# sensor.net
KiCad netlist of a schematic drawn in Altium Designer
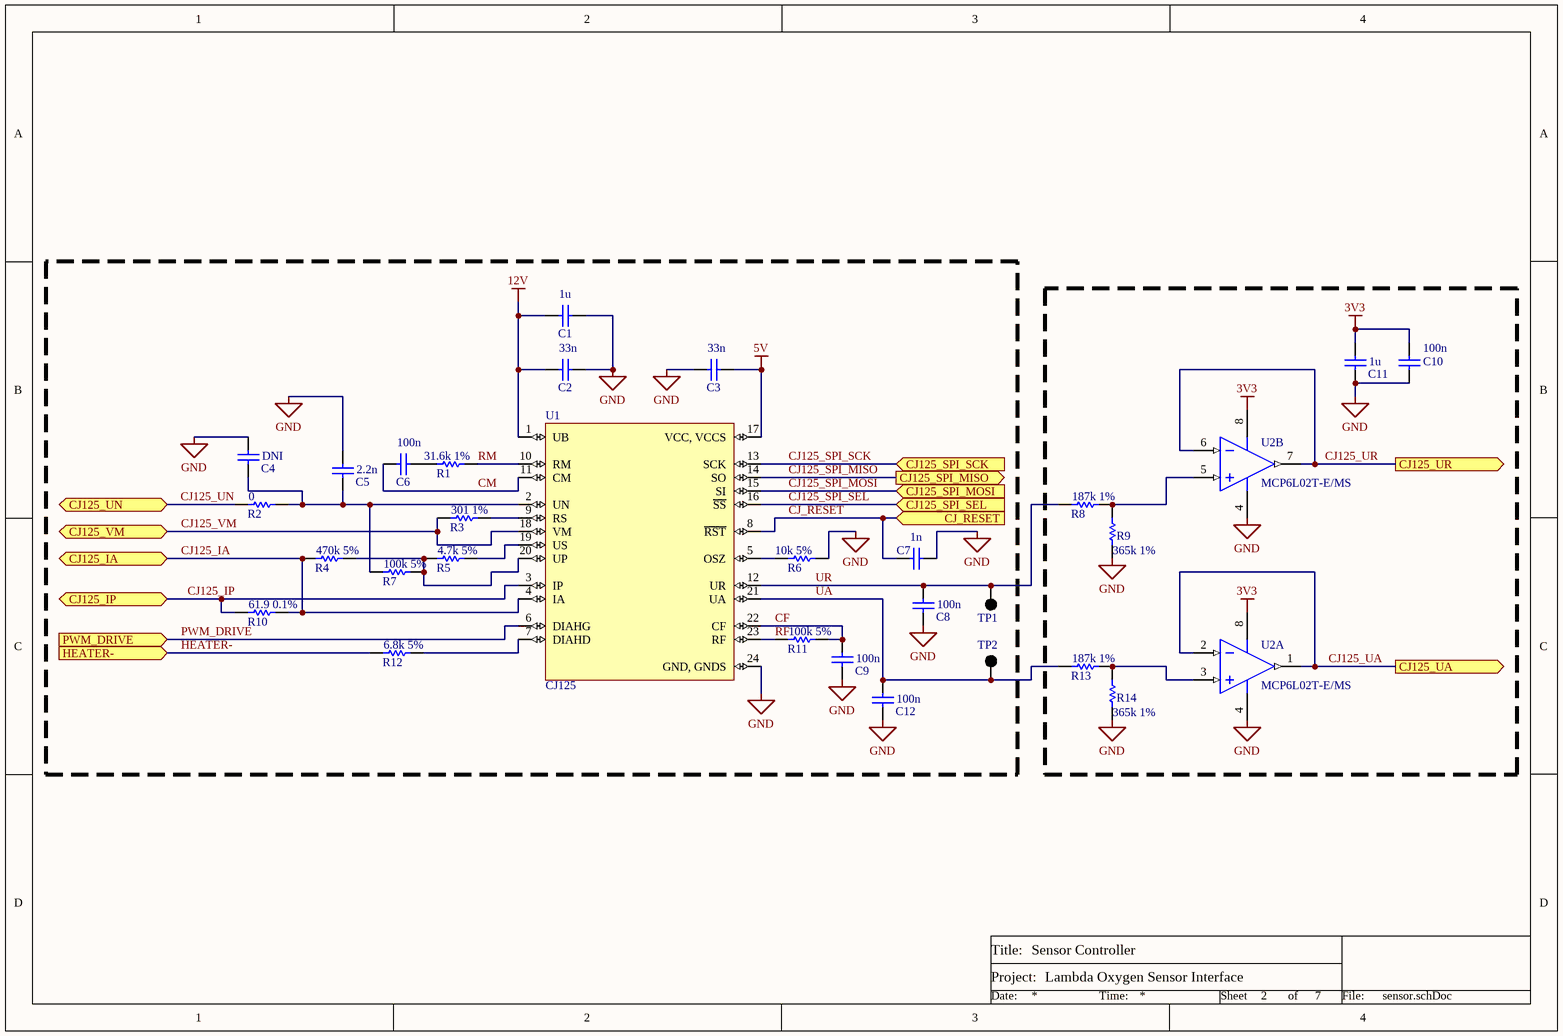
[diagram p0: sensor.schDoc]

(export (version "E")
  (design (tool "Eeschema 10.0.6"))
  (components
    (comp (ref "C1")
      (value "1u")
      (footprint "1206")
      (description "Generic 1206 Capacitor")
      (libsource (lib "symbol_library") (part "C_1206"))
    )
    (comp (ref "C2")
      (value "33n")
      (footprint "0805")
      (description "Generic 0805 Capacitor")
      (libsource (lib "symbol_library") (part "C_0805"))
    )
    (comp (ref "C3")
      (value "33n")
      (footprint "0805")
      (description "Generic 0805 Capacitor")
      (libsource (lib "symbol_library") (part "C_0805"))
    )
    (comp (ref "C4")
      (value "DNI")
      (footprint "0805")
      (description "Generic 0805 Capacitor")
      (libsource (lib "symbol_library") (part "C_0805"))
    )
    (comp (ref "C5")
      (value "2.2n")
      (footprint "0805")
      (description "Generic 0805 Capacitor")
      (libsource (lib "symbol_library") (part "C_0805"))
    )
    (comp (ref "C6")
      (value "100n")
      (footprint "0805")
      (description "Generic 0805 Capacitor")
      (libsource (lib "symbol_library") (part "C_0805"))
    )
    (comp (ref "C7")
      (value "1n")
      (footprint "0805")
      (description "Generic 0805 Capacitor")
      (libsource (lib "symbol_library") (part "C_0805"))
    )
    (comp (ref "C8")
      (value "100n")
      (footprint "0805")
      (description "Generic 0805 Capacitor")
      (libsource (lib "symbol_library") (part "C_0805"))
    )
    (comp (ref "C9")
      (value "100n")
      (footprint "0805")
      (description "Generic 0805 Capacitor")
      (libsource (lib "symbol_library") (part "C_0805"))
    )
    (comp (ref "C10")
      (value "100n")
      (footprint "0805")
      (description "Generic 0805 Capacitor")
      (libsource (lib "symbol_library") (part "C_0805"))
    )
    (comp (ref "C11")
      (value "1u")
      (footprint "1206")
      (description "Generic 1206 Capacitor")
      (libsource (lib "symbol_library") (part "C_1206"))
    )
    (comp (ref "C12")
      (value "100n")
      (footprint "0805")
      (description "Generic 0805 Capacitor")
      (libsource (lib "symbol_library") (part "C_0805"))
    )
    (comp (ref "R1")
      (value "31.6k 1%")
      (footprint "0603")
      (description "Generic 0603 Resistor")
      (libsource (lib "symbol_library") (part "R_0603"))
    )
    (comp (ref "R2")
      (value "0")
      (footprint "0603")
      (description "Generic 0603 Resistor")
      (libsource (lib "symbol_library") (part "R_0603"))
    )
    (comp (ref "R3")
      (value "301 1%")
      (footprint "0603")
      (description "Generic 0603 Resistor")
      (libsource (lib "symbol_library") (part "R_0603"))
    )
    (comp (ref "R4")
      (value "470k 5%")
      (footprint "0603")
      (description "Generic 0603 Resistor")
      (libsource (lib "symbol_library") (part "R_0603"))
    )
    (comp (ref "R5")
      (value "4.7k 5%")
      (footprint "0603")
      (description "Generic 0603 Resistor")
      (libsource (lib "symbol_library") (part "R_0603"))
    )
    (comp (ref "R6")
      (value "10k 5%")
      (footprint "0603")
      (description "Generic 0603 Resistor")
      (libsource (lib "symbol_library") (part "R_0603"))
    )
    (comp (ref "R7")
      (value "100k 5%")
      (footprint "0603")
      (description "Generic 0603 Resistor")
      (libsource (lib "symbol_library") (part "R_0603"))
    )
    (comp (ref "R8")
      (value "187k 1%")
      (footprint "0603")
      (description "Generic 0603 Resistor")
      (libsource (lib "symbol_library") (part "R_0603"))
    )
    (comp (ref "R9")
      (value "365k 1%")
      (footprint "0603")
      (description "Generic 0603 Resistor")
      (libsource (lib "symbol_library") (part "R_0603"))
    )
    (comp (ref "R10")
      (value "61.9 0.1%")
      (footprint "0603")
      (description "Generic 0603 Resistor")
      (libsource (lib "symbol_library") (part "R_0603"))
    )
    (comp (ref "R11")
      (value "100k 5%")
      (footprint "0603")
      (description "Generic 0603 Resistor")
      (libsource (lib "symbol_library") (part "R_0603"))
    )
    (comp (ref "R12")
      (value "6.8k 5%")
      (footprint "0603")
      (description "Generic 0603 Resistor")
      (libsource (lib "symbol_library") (part "R_0603"))
    )
    (comp (ref "R13")
      (value "187k 1%")
      (footprint "0603")
      (description "Generic 0603 Resistor")
      (libsource (lib "symbol_library") (part "R_0603"))
    )
    (comp (ref "R14")
      (value "365k 1%")
      (footprint "0603")
      (description "Generic 0603 Resistor")
      (libsource (lib "symbol_library") (part "R_0603"))
    )
    (comp (ref "TP1")
      (value "5001")
      (footprint "KSTN-5001")
      (description "Test Point, Black, 1-Pin THD, RoHS, Bulk")
      (fields (field (name "MANUFACTURER") "Keystone"))
      (libsource (lib "symbol_library") (part "TP5001"))
    )
    (comp (ref "TP2")
      (value "5001")
      (footprint "KSTN-5001")
      (description "Test Point, Black, 1-Pin THD, RoHS, Bulk")
      (fields (field (name "MANUFACTURER") "Keystone"))
      (libsource (lib "symbol_library") (part "TP5001"))
    )
    (comp (ref "U1")
      (value "CJ125")
      (footprint "SOIC-24")
      (description "5V 2Mbaud SMT Lambda Probe Interface IC - SOIC-24")
      (libsource (lib "symbol_library") (part "CJ125"))
    )
    (comp (ref "U2")
      (value "MCP6L02T-E/MS")
      (footprint "MSOP8_M")
      (description "1 MHz, 85 渭A Dual Op Amp, 8-Pin MSOP, Extended Temperature Range, Tape and Reel")
      (libsource (lib "symbol_library") (part "MCP6L02"))
    )
  )
  (nets
    (net (code "1") (name "/CF") (class "Default")
      (node (ref "C9") (pin "2") (pinfunction "2_2") (pintype "passive"))
      (node (ref "R11") (pin "2") (pinfunction "2_2") (pintype "passive"))
      (node (ref "U1") (pin "22") (pinfunction "CF_22") (pintype "bidirectional"))
    )
    (net (code "2") (name "/CJ125_IA") (class "Default")
      (node (ref "R10") (pin "2") (pinfunction "2_2") (pintype "passive"))
      (node (ref "R4") (pin "1") (pinfunction "1_1") (pintype "passive"))
      (node (ref "U1") (pin "4") (pinfunction "IA_4") (pintype "bidirectional"))
    )
    (net (code "3") (name "/CJ125_IP") (class "Default")
      (node (ref "R10") (pin "1") (pinfunction "1_1") (pintype "passive"))
      (node (ref "U1") (pin "3") (pinfunction "IP_3") (pintype "bidirectional"))
    )
    (net (code "4") (name "/CJ125_SPI_MISO") (class "Default")
      (node (ref "U1") (pin "14") (pinfunction "SO_14") (pintype "bidirectional"))
    )
    (net (code "5") (name "/CJ125_SPI_MOSI") (class "Default")
      (node (ref "U1") (pin "15") (pinfunction "SI_15") (pintype "bidirectional"))
    )
    (net (code "6") (name "/CJ125_SPI_SCK") (class "Default")
      (node (ref "U1") (pin "13") (pinfunction "SCK_13") (pintype "bidirectional"))
    )
    (net (code "7") (name "/CJ125_SPI_SEL") (class "Default")
      (node (ref "U1") (pin "16") (pinfunction "~{SS}_16") (pintype "bidirectional"))
    )
    (net (code "8") (name "/CJ125_UA") (class "Default")
      (node (ref "U2") (pin "1") (pinfunction "VOUTA_1") (pintype "output"))
      (node (ref "U2") (pin "2") (pinfunction "VINA-_2") (pintype "input"))
    )
    (net (code "9") (name "/CJ125_UN") (class "Default")
      (node (ref "R2") (pin "1") (pinfunction "1_1") (pintype "passive"))
    )
    (net (code "10") (name "/CJ125_UR") (class "Default")
      (node (ref "U2") (pin "6") (pinfunction "VINB-_6") (pintype "input"))
      (node (ref "U2") (pin "7") (pinfunction "VOUTB_7") (pintype "output"))
    )
    (net (code "11") (name "/CJ125_VM") (class "Default")
      (node (ref "R3") (pin "1") (pinfunction "1_1") (pintype "passive"))
      (node (ref "U1") (pin "18") (pinfunction "VM_18") (pintype "bidirectional"))
    )
    (net (code "12") (name "/CJ_RESET") (class "Default")
      (node (ref "C7") (pin "1") (pinfunction "1_1") (pintype "passive"))
      (node (ref "U1") (pin "8") (pinfunction "~{RST}_8") (pintype "bidirectional"))
    )
    (net (code "13") (name "/CM") (class "Default")
      (node (ref "C6") (pin "1") (pinfunction "1_1") (pintype "passive"))
      (node (ref "U1") (pin "11") (pinfunction "CM_11") (pintype "bidirectional"))
    )
    (net (code "14") (name "/HEATER-") (class "Default")
      (node (ref "R12") (pin "1") (pinfunction "1_1") (pintype "passive"))
    )
    (net (code "15") (name "/PWM_DRIVE") (class "Default")
      (node (ref "U1") (pin "6") (pinfunction "DIAHG_6") (pintype "bidirectional"))
    )
    (net (code "16") (name "/RF") (class "Default")
      (node (ref "R11") (pin "1") (pinfunction "1_1") (pintype "passive"))
      (node (ref "U1") (pin "23") (pinfunction "RF_23") (pintype "bidirectional"))
    )
    (net (code "17") (name "/RM") (class "Default")
      (node (ref "R1") (pin "2") (pinfunction "2_2") (pintype "passive"))
      (node (ref "U1") (pin "10") (pinfunction "RM_10") (pintype "bidirectional"))
    )
    (net (code "18") (name "/UA") (class "Default")
      (node (ref "C12") (pin "2") (pinfunction "2_2") (pintype "passive"))
      (node (ref "R13") (pin "1") (pinfunction "1_1") (pintype "passive"))
      (node (ref "TP2") (pin "1") (pintype "passive"))
      (node (ref "U1") (pin "21") (pinfunction "UA_21") (pintype "bidirectional"))
    )
    (net (code "19") (name "/UR") (class "Default")
      (node (ref "C8") (pin "2") (pinfunction "2_2") (pintype "passive"))
      (node (ref "R8") (pin "1") (pinfunction "1_1") (pintype "passive"))
      (node (ref "TP1") (pin "1") (pintype "passive"))
      (node (ref "U1") (pin "12") (pinfunction "UR_12") (pintype "bidirectional"))
    )
    (net (code "20") (name "3V3") (class "Default")
      (node (ref "C10") (pin "2") (pinfunction "2_2") (pintype "passive"))
      (node (ref "C11") (pin "2") (pinfunction "2_2") (pintype "passive"))
      (node (ref "U2") (pin "8") (pinfunction "VDD_8") (pintype "power_in"))
    )
    (net (code "21") (name "5V") (class "Default")
      (node (ref "C3") (pin "1") (pinfunction "1_1") (pintype "passive"))
      (node (ref "U1") (pin "17") (pinfunction "VCC,_VCCS_17") (pintype "bidirectional"))
    )
    (net (code "22") (name "12V") (class "Default")
      (node (ref "C1") (pin "1") (pinfunction "1_1") (pintype "passive"))
      (node (ref "C2") (pin "2") (pinfunction "2_2") (pintype "passive"))
      (node (ref "U1") (pin "1") (pinfunction "UB_1") (pintype "bidirectional"))
    )
    (net (code "23") (name "GND") (class "Default")
      (node (ref "C1") (pin "2") (pinfunction "2_2") (pintype "passive"))
      (node (ref "C10") (pin "1") (pinfunction "1_1") (pintype "passive"))
      (node (ref "C11") (pin "1") (pinfunction "1_1") (pintype "passive"))
      (node (ref "C12") (pin "1") (pinfunction "1_1") (pintype "passive"))
      (node (ref "C2") (pin "1") (pinfunction "1_1") (pintype "passive"))
      (node (ref "C3") (pin "2") (pinfunction "2_2") (pintype "passive"))
      (node (ref "C4") (pin "2") (pinfunction "2_2") (pintype "passive"))
      (node (ref "C5") (pin "2") (pinfunction "2_2") (pintype "passive"))
      (node (ref "C7") (pin "2") (pinfunction "2_2") (pintype "passive"))
      (node (ref "C8") (pin "1") (pinfunction "1_1") (pintype "passive"))
      (node (ref "C9") (pin "1") (pinfunction "1_1") (pintype "passive"))
      (node (ref "R14") (pin "1") (pinfunction "1_1") (pintype "passive"))
      (node (ref "R6") (pin "2") (pinfunction "2_2") (pintype "passive"))
      (node (ref "R9") (pin "1") (pinfunction "1_1") (pintype "passive"))
      (node (ref "U1") (pin "24") (pinfunction "GND,_GNDS_24") (pintype "bidirectional"))
      (node (ref "U2") (pin "4") (pinfunction "VSS_4") (pintype "power_in"))
    )
    (net (code "24") (name "Net-(C6-Pad2)") (class "Default")
      (node (ref "C6") (pin "2") (pinfunction "2_2") (pintype "passive"))
      (node (ref "R1") (pin "1") (pinfunction "1_1") (pintype "passive"))
    )
    (net (code "25") (name "Net-(U1-DIAHD)") (class "Default")
      (node (ref "R12") (pin "2") (pinfunction "2_2") (pintype "passive"))
      (node (ref "U1") (pin "7") (pinfunction "DIAHD_7") (pintype "bidirectional"))
    )
    (net (code "26") (name "Net-(U1-OSZ)") (class "Default")
      (node (ref "R6") (pin "1") (pinfunction "1_1") (pintype "passive"))
      (node (ref "U1") (pin "5") (pinfunction "OSZ_5") (pintype "bidirectional"))
    )
    (net (code "27") (name "Net-(U1-RS)") (class "Default")
      (node (ref "R3") (pin "2") (pinfunction "2_2") (pintype "passive"))
      (node (ref "U1") (pin "9") (pinfunction "RS_9") (pintype "bidirectional"))
    )
    (net (code "28") (name "Net-(U1-UN)") (class "Default")
      (node (ref "C4") (pin "1") (pinfunction "1_1") (pintype "passive"))
      (node (ref "C5") (pin "1") (pinfunction "1_1") (pintype "passive"))
      (node (ref "R2") (pin "2") (pinfunction "2_2") (pintype "passive"))
      (node (ref "R7") (pin "1") (pinfunction "1_1") (pintype "passive"))
      (node (ref "U1") (pin "2") (pinfunction "UN_2") (pintype "bidirectional"))
    )
    (net (code "29") (name "Net-(U1-UP)") (class "Default")
      (node (ref "R4") (pin "2") (pinfunction "2_2") (pintype "passive"))
      (node (ref "R5") (pin "1") (pinfunction "1_1") (pintype "passive"))
      (node (ref "R7") (pin "2") (pinfunction "2_2") (pintype "passive"))
      (node (ref "U1") (pin "20") (pinfunction "UP_20") (pintype "bidirectional"))
    )
    (net (code "30") (name "Net-(U1-US)") (class "Default")
      (node (ref "R5") (pin "2") (pinfunction "2_2") (pintype "passive"))
      (node (ref "U1") (pin "19") (pinfunction "US_19") (pintype "bidirectional"))
    )
    (net (code "31") (name "Net-(U2A-VINA+)") (class "Default")
      (node (ref "R13") (pin "2") (pinfunction "2_2") (pintype "passive"))
      (node (ref "R14") (pin "2") (pinfunction "2_2") (pintype "passive"))
      (node (ref "U2") (pin "3") (pinfunction "VINA+_3") (pintype "input"))
    )
    (net (code "32") (name "Net-(U2B-VINB+)") (class "Default")
      (node (ref "R8") (pin "2") (pinfunction "2_2") (pintype "passive"))
      (node (ref "R9") (pin "2") (pinfunction "2_2") (pintype "passive"))
      (node (ref "U2") (pin "5") (pinfunction "VINB+_5") (pintype "input"))
    )
  )
)
